# design.net
KiCad netlist of a schematic drawn in Altium Designer
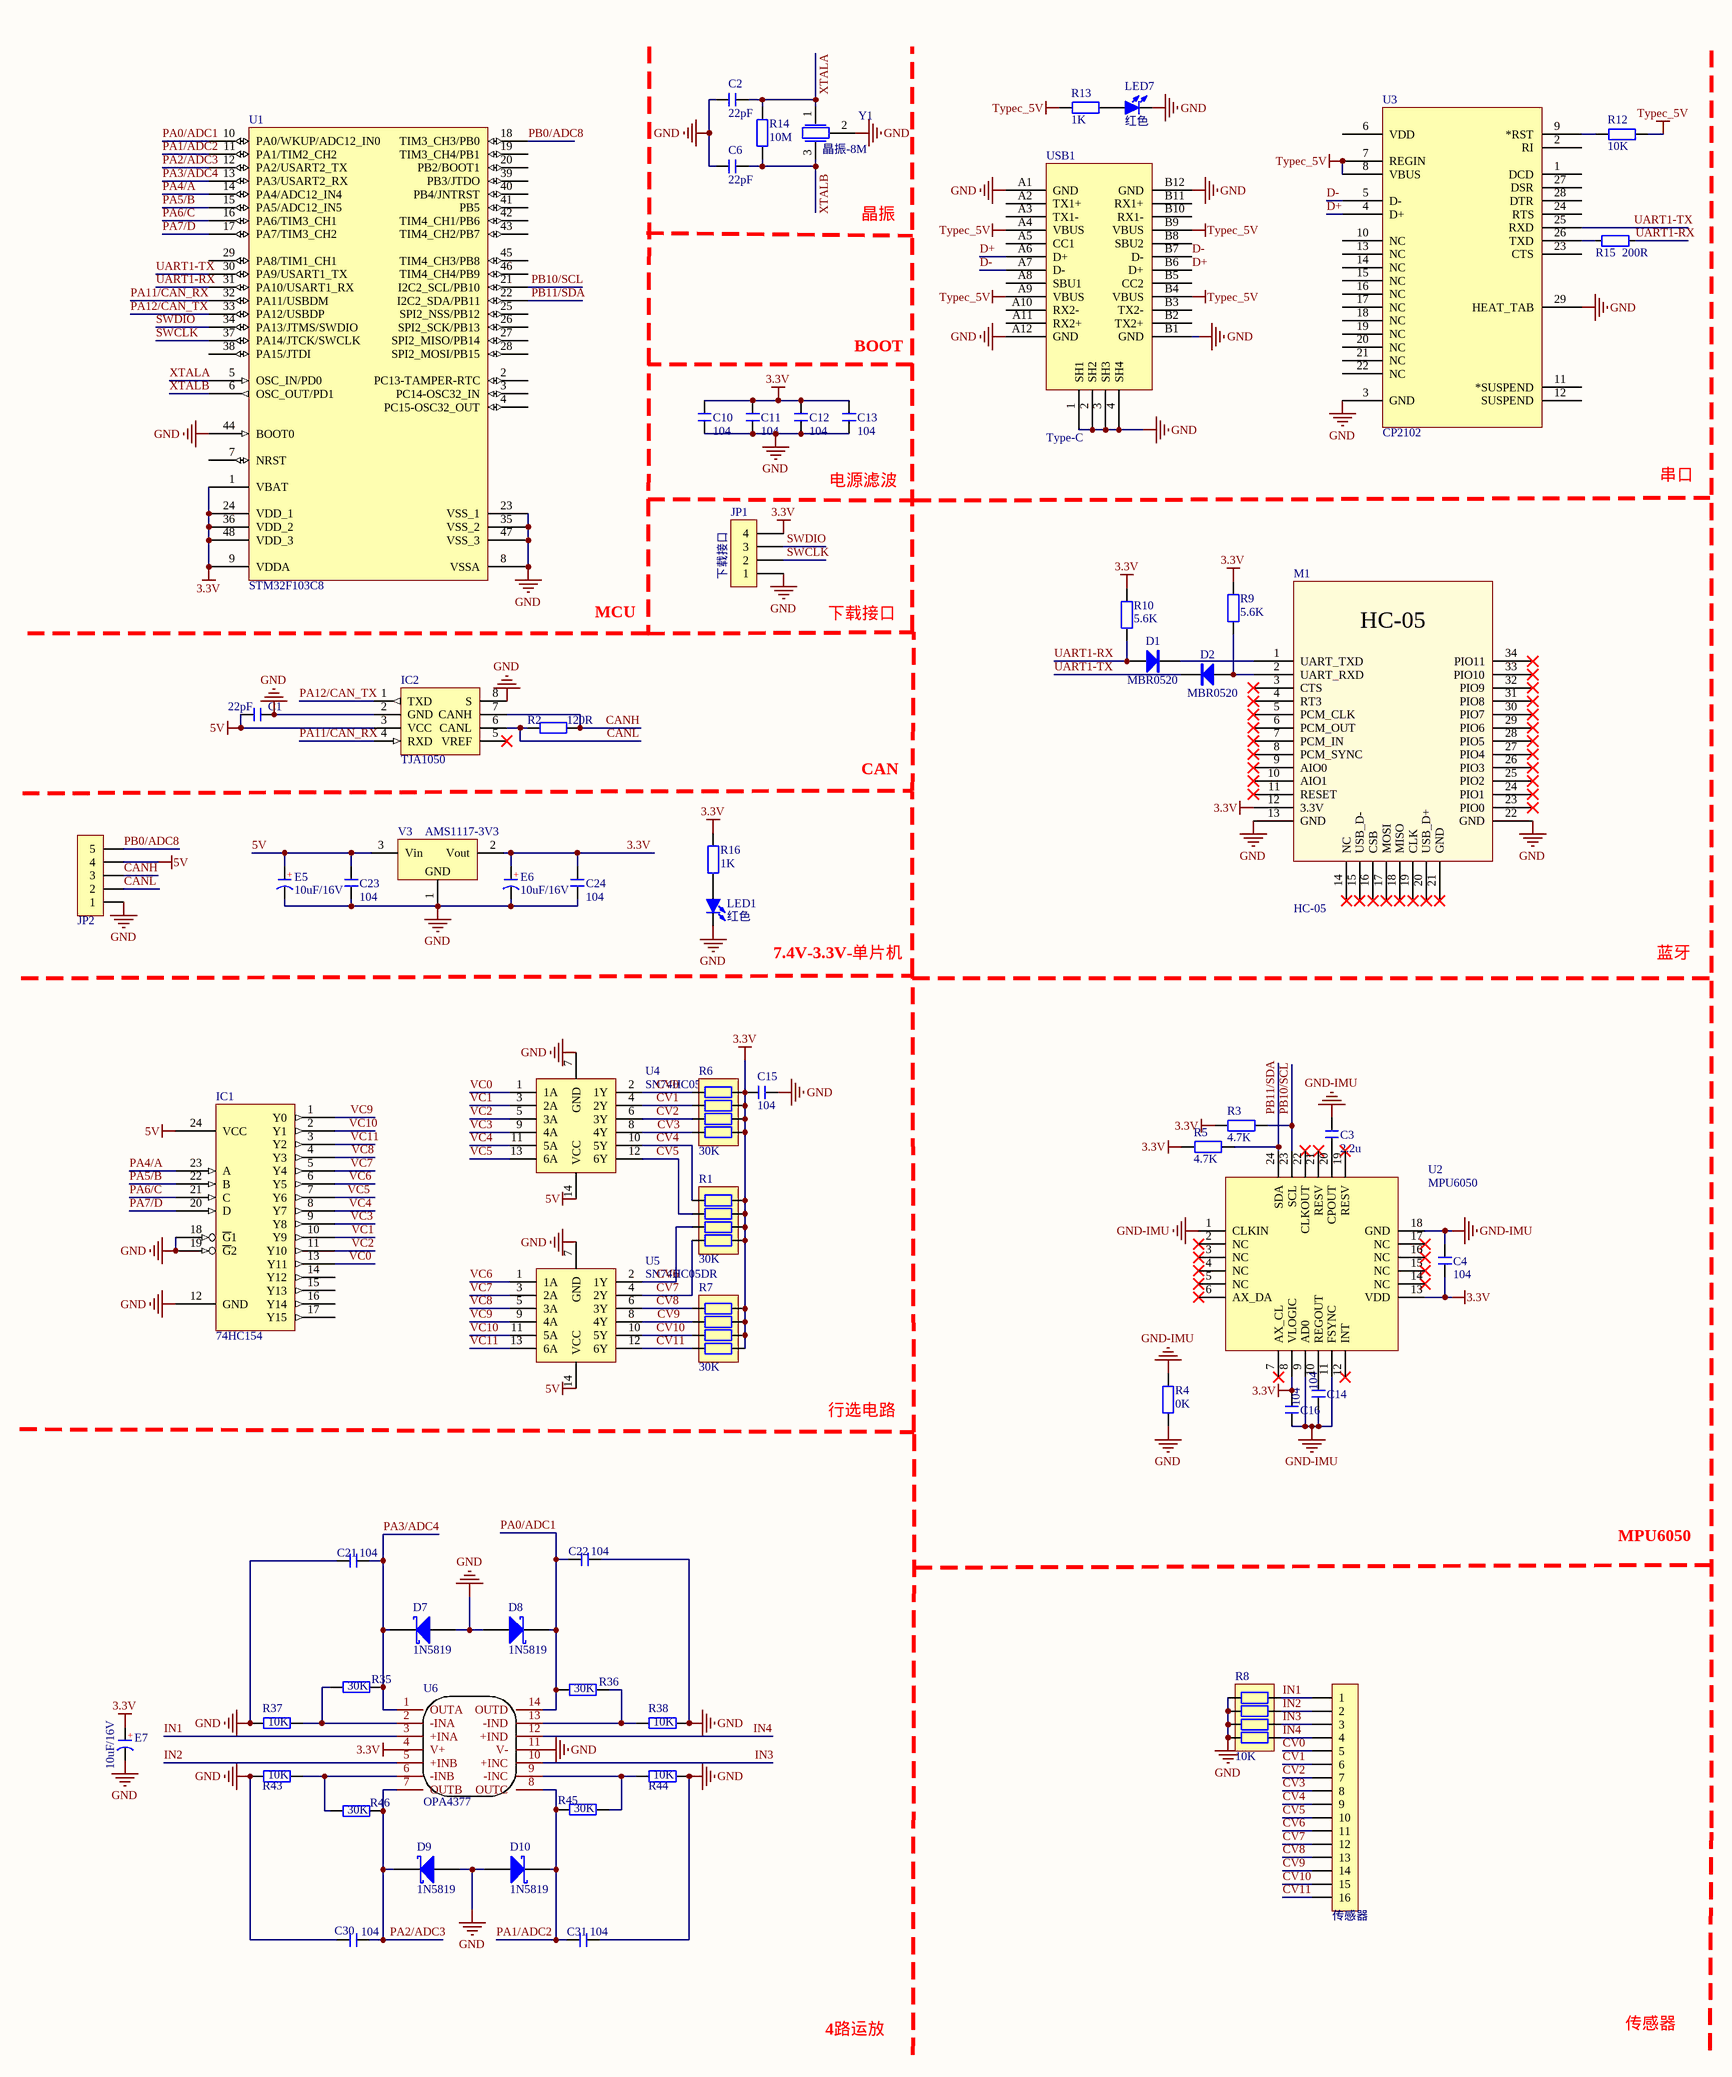
[diagram p0: 足底压力.SchDoc]

(export (version "E")
  (design (tool "Eeschema 10.0.6"))
  (components
    (comp (ref "C1")
      (value "22pF")
      (footprint "C 0402_L")
      (description "贴片电容")
      (libsource (lib "0.1 - 电阻-电容-电感") (part "C"))
    )
    (comp (ref "C2")
      (value "22pF")
      (footprint "C 0402_L")
      (description "贴片电容")
      (libsource (lib "0.1 - 电阻-电容-电感") (part "C"))
    )
    (comp (ref "C3")
      (value "2.2u")
      (footprint "C 0402_L")
      (description "贴片电容")
      (libsource (lib "0.1 - 电阻-电容-电感") (part "C"))
    )
    (comp (ref "C4")
      (value "104")
      (footprint "C 0402_L")
      (description "贴片电容")
      (libsource (lib "0.1 - 电阻-电容-电感") (part "C"))
    )
    (comp (ref "C6")
      (value "22pF")
      (footprint "C 0402_L")
      (description "贴片电容")
      (libsource (lib "0.1 - 电阻-电容-电感") (part "C"))
    )
    (comp (ref "C10")
      (value "104")
      (footprint "C 0402_L")
      (description "贴片电容")
      (libsource (lib "0.1 - 电阻-电容-电感") (part "C"))
    )
    (comp (ref "C11")
      (value "104")
      (footprint "C 0402_L")
      (description "贴片电容")
      (libsource (lib "0.1 - 电阻-电容-电感") (part "C"))
    )
    (comp (ref "C12")
      (value "104")
      (footprint "C 0402_L")
      (description "贴片电容")
      (libsource (lib "0.1 - 电阻-电容-电感") (part "C"))
    )
    (comp (ref "C13")
      (value "104")
      (footprint "C 0402_L")
      (description "贴片电容")
      (libsource (lib "0.1 - 电阻-电容-电感") (part "C"))
    )
    (comp (ref "C14")
      (value "104")
      (footprint "C 0402_L")
      (description "贴片电容")
      (libsource (lib "0.1 - 电阻-电容-电感") (part "C"))
    )
    (comp (ref "C15")
      (value "104")
      (footprint "C 0402_L")
      (description "贴片电容")
      (libsource (lib "0.1 - 电阻-电容-电感") (part "C"))
    )
    (comp (ref "C16")
      (value "104")
      (footprint "C 0402_L")
      (description "贴片电容")
      (libsource (lib "0.1 - 电阻-电容-电感") (part "C"))
    )
    (comp (ref "C21")
      (value "104")
      (footprint "C 0402_L")
      (description "贴片电容")
      (libsource (lib "0.1 - 电阻-电容-电感") (part "C"))
    )
    (comp (ref "C22")
      (value "104")
      (footprint "C 0402_L")
      (description "贴片电容")
      (libsource (lib "0.1 - 电阻-电容-电感") (part "C"))
    )
    (comp (ref "C23")
      (value "104")
      (footprint "C 0402_L")
      (description "贴片电容")
      (libsource (lib "0.1 - 电阻-电容-电感") (part "C"))
    )
    (comp (ref "C24")
      (value "104")
      (footprint "C 0402_L")
      (description "贴片电容")
      (libsource (lib "0.1 - 电阻-电容-电感") (part "C"))
    )
    (comp (ref "C30")
      (value "104")
      (footprint "C 0402_L")
      (description "贴片电容")
      (libsource (lib "0.1 - 电阻-电容-电感") (part "C"))
    )
    (comp (ref "C31")
      (value "104")
      (footprint "C 0402_L")
      (description "贴片电容")
      (libsource (lib "0.1 - 电阻-电容-电感") (part "C"))
    )
    (comp (ref "D1")
      (value "MBR0520")
      (footprint "SOD-123")
      (description "整流二极管")
      (libsource (lib "0.2 -  二极管-整流桥") (part "1N4007"))
    )
    (comp (ref "D2")
      (value "MBR0520")
      (footprint "SOD-123")
      (description "整流二极管")
      (libsource (lib "0.2 -  二极管-整流桥") (part "1N4007"))
    )
    (comp (ref "D7")
      (value "1N5819")
      (footprint "SOD-123")
      (description "肖特基二极管")
      (libsource (lib "0.2 -  二极管-整流桥") (part "1N5819"))
    )
    (comp (ref "D8")
      (value "1N5819")
      (footprint "SOD-123")
      (description "肖特基二极管")
      (libsource (lib "0.2 -  二极管-整流桥") (part "1N5819"))
    )
    (comp (ref "D9")
      (value "1N5819")
      (footprint "SOD-123")
      (description "肖特基二极管")
      (libsource (lib "0.2 -  二极管-整流桥") (part "1N5819"))
    )
    (comp (ref "D10")
      (value "1N5819")
      (footprint "SOD-123")
      (description "肖特基二极管")
      (libsource (lib "0.2 -  二极管-整流桥") (part "1N5819"))
    )
    (comp (ref "E5")
      (value "10uF/16V")
      (footprint "CD A(3216)")
      (description "贴片钽电容")
      (libsource (lib "0.1 - 电阻-电容-电感") (part "CT"))
    )
    (comp (ref "E6")
      (value "10uF/16V")
      (footprint "CD A(3216)")
      (description "贴片钽电容")
      (libsource (lib "0.1 - 电阻-电容-电感") (part "CT"))
    )
    (comp (ref "E7")
      (value "10uF/16V")
      (footprint "CD A(3216)")
      (description "贴片钽电容")
      (libsource (lib "0.1 - 电阻-电容-电感") (part "CT"))
    )
    (comp (ref "IC1")
      (value "74HC154")
      (footprint "SOP24_N")
      (description "4线转16线译码器")
      (libsource (lib "74系列芯片") (part "74HC154"))
    )
    (comp (ref "IC2")
      (value "TJA1050")
      (footprint "SOP8_L")
      (description "CAN总线收发芯片")
      (libsource (lib "1.0 - 常见芯片") (part "TJA1050"))
    )
    (comp (ref "JP1")
      (value "下载接口")
      (footprint "下载接口")
      (description "Jlink下载接口")
      (libsource (lib "金手指") (part "下载接口"))
    )
    (comp (ref "JP2")
      (value "HDR-1X5")
      (footprint "HDR2.54-M-LI-5P")
      (description "5P接插件")
      (libsource (lib "5.3 - 接插件-脚距2.54 (100mil) ") (part "Header 5"))
    )
    (comp (ref "LED1")
      (value "红色")
      (footprint "LED 0603R")
      (description "贴片LED")
      (libsource (lib "0.3 - LED发光二极管") (part "LED-SMD"))
    )
    (comp (ref "LED7")
      (value "红色")
      (footprint "LED 0603R")
      (description "贴片LED")
      (libsource (lib "0.3 - LED发光二极管") (part "LED-SMD"))
    )
    (comp (ref "M1")
      (value "HC-05")
      (footprint "HC-05")
      (description "串口蓝牙模块")
      (libsource (lib "模块") (part "HC-05"))
    )
    (comp (ref "R1")
      (value "30K")
      (footprint "RCA-8P4R-0603")
      (description "贴片排阻")
      (libsource (lib "0.1 - 电阻-电容-电感") (part "R-8P4R"))
    )
    (comp (ref "R2")
      (value "120R")
      (footprint "R 0402_L")
      (description "贴片电阻")
      (libsource (lib "0.1 - 电阻-电容-电感") (part "R"))
    )
    (comp (ref "R3")
      (value "4.7K")
      (footprint "R 0402_L")
      (description "贴片电阻")
      (libsource (lib "0.1 - 电阻-电容-电感") (part "R"))
    )
    (comp (ref "R4")
      (value "0K")
      (footprint "R 0402_L")
      (description "贴片电阻")
      (libsource (lib "0.1 - 电阻-电容-电感") (part "R"))
    )
    (comp (ref "R5")
      (value "4.7K")
      (footprint "R 0402_L")
      (description "贴片电阻")
      (libsource (lib "0.1 - 电阻-电容-电感") (part "R"))
    )
    (comp (ref "R6")
      (value "30K")
      (footprint "RCA-8P4R-0603")
      (description "贴片排阻")
      (libsource (lib "0.1 - 电阻-电容-电感") (part "R-8P4R"))
    )
    (comp (ref "R7")
      (value "30K")
      (footprint "RCA-8P4R-0603")
      (description "贴片排阻")
      (libsource (lib "0.1 - 电阻-电容-电感") (part "R-8P4R"))
    )
    (comp (ref "R8")
      (value "10K")
      (footprint "RCA-8P4R-0603")
      (description "贴片排阻")
      (libsource (lib "") (part "R-8P4R_1"))
    )
    (comp (ref "R9")
      (value "5.6K")
      (footprint "R 0402_L")
      (description "贴片电阻")
      (libsource (lib "0.1 - 电阻-电容-电感") (part "R"))
    )
    (comp (ref "R10")
      (value "5.6K")
      (footprint "R 0402_L")
      (description "贴片电阻")
      (libsource (lib "0.1 - 电阻-电容-电感") (part "R"))
    )
    (comp (ref "R12")
      (value "10K")
      (footprint "R 0402_L")
      (description "贴片电阻")
      (libsource (lib "0.1 - 电阻-电容-电感") (part "R"))
    )
    (comp (ref "R13")
      (value "1K")
      (footprint "R 0402_L")
      (description "贴片电阻")
      (libsource (lib "0.1 - 电阻-电容-电感") (part "R"))
    )
    (comp (ref "R14")
      (value "10M")
      (footprint "R 0402_L")
      (description "贴片电阻")
      (libsource (lib "0.1 - 电阻-电容-电感") (part "R"))
    )
    (comp (ref "R15")
      (value "200R")
      (footprint "RES_0402")
      (description "Resistor")
      (libsource (lib "MyPcbLib") (part "电阻-0402"))
    )
    (comp (ref "R16")
      (value "1K")
      (footprint "R 0402_L")
      (description "贴片电阻")
      (libsource (lib "0.1 - 电阻-电容-电感") (part "R"))
    )
    (comp (ref "R35")
      (value "30K")
      (footprint "R 0402_L")
      (description "贴片电阻")
      (libsource (lib "0.1 - 电阻-电容-电感") (part "R"))
    )
    (comp (ref "R36")
      (value "30K")
      (footprint "R 0402_L")
      (description "贴片电阻")
      (libsource (lib "0.1 - 电阻-电容-电感") (part "R"))
    )
    (comp (ref "R37")
      (value "10K")
      (footprint "R 0402_L")
      (description "贴片电阻")
      (libsource (lib "0.1 - 电阻-电容-电感") (part "R"))
    )
    (comp (ref "R38")
      (value "10K")
      (footprint "R 0402_L")
      (description "贴片电阻")
      (libsource (lib "0.1 - 电阻-电容-电感") (part "R"))
    )
    (comp (ref "R43")
      (value "10K")
      (footprint "R 0402_L")
      (description "贴片电阻")
      (libsource (lib "0.1 - 电阻-电容-电感") (part "R"))
    )
    (comp (ref "R44")
      (value "10K")
      (footprint "R 0402_L")
      (description "贴片电阻")
      (libsource (lib "0.1 - 电阻-电容-电感") (part "R"))
    )
    (comp (ref "R45")
      (value "30K")
      (footprint "R 0402_L")
      (description "贴片电阻")
      (libsource (lib "0.1 - 电阻-电容-电感") (part "R"))
    )
    (comp (ref "R46")
      (value "30K")
      (footprint "R 0402_L")
      (description "贴片电阻")
      (libsource (lib "0.1 - 电阻-电容-电感") (part "R"))
    )
    (comp (ref "U1")
      (value "STM32F103C8")
      (footprint "LQFP48 7X7_L")
      (description "Flaah:64/RAM:20/IO:36")
      (libsource (lib "STM32系列单片机") (part "STM32F103C8"))
    )
    (comp (ref "U2")
      (value "MPU6050")
      (footprint "QFN24 4x4_L")
      (description "数字运动传感器")
      (libsource (lib "传感元件") (part "MPU6050"))
    )
    (comp (ref "U3")
      (value "CP2102")
      (footprint "QFN-28")
      (description "USB转TTL")
      (libsource (lib "mLib") (part "CP2102"))
    )
    (comp (ref "U4")
      (value "SN74HC05DR")
      (footprint "SOP14")
      (libsource (lib "1.4 - 74系列TTL芯片") (part "SN74HC05DR"))
    )
    (comp (ref "U5")
      (value "SN74HC05DR")
      (footprint "SOP14")
      (libsource (lib "1.4 - 74系列TTL芯片") (part "SN74HC05DR"))
    )
    (comp (ref "U6")
      (value "OPA4377")
      (footprint "TSSOP14_L")
      (description "4路运放")
      (libsource (lib "运放-功放") (part "OPA4377"))
    )
    (comp (ref "USB1")
      (value "Type-C")
      (footprint "USB-C-SMD_16P")
      (libsource (lib "0.8 - 以太网-音频-USB插座") (part "USB-Type-C-TOP"))
    )
    (comp (ref "V3")
      (value "AMS1117-3V3")
      (footprint "SOT223_L")
      (description "三端稳压芯片")
      (libsource (lib "1.1 - 电源类芯片") (part "AMS1117"))
    )
    (comp (ref "Y1")
      (value "晶振-8M")
      (footprint "XTAL3*7")
      (libsource (lib "2.0 - 保险丝-晶振-光耦") (part "XTAL-3P"))
    )
    (comp (ref "传感器")
      (value "HDR-1X16")
      (footprint "XH2.54-WI-16P")
      (description "16P接插件")
      (libsource (lib "5.3 - 接插件-脚距2.54 (100mil) ") (part "Header 16"))
    )
  )
  (nets
    (net (code "1") (name "/CANH") (class "Default")
      (node (ref "IC2") (pin "7") (pinfunction "CANH_7") (pintype "passive"))
      (node (ref "JP2") (pin "3") (pinfunction "3_3") (pintype "passive"))
      (node (ref "R2") (pin "1") (pinfunction "1_1") (pintype "passive"))
    )
    (net (code "2") (name "/CANL") (class "Default")
      (node (ref "IC2") (pin "6") (pinfunction "CANL_6") (pintype "passive"))
      (node (ref "JP2") (pin "2") (pinfunction "2_2") (pintype "passive"))
      (node (ref "R2") (pin "2") (pinfunction "2_2") (pintype "passive"))
    )
    (net (code "3") (name "/CV0") (class "Default")
      (node (ref "R6") (pin "1") (pinfunction "1_1") (pintype "passive"))
      (node (ref "U4") (pin "2") (pinfunction "1Y_2") (pintype "passive"))
      (node (ref "传感器") (pin "5") (pinfunction "5_5") (pintype "passive"))
    )
    (net (code "4") (name "/CV1") (class "Default")
      (node (ref "R6") (pin "2") (pinfunction "2_2") (pintype "passive"))
      (node (ref "U4") (pin "4") (pinfunction "2Y_4") (pintype "passive"))
      (node (ref "传感器") (pin "6") (pinfunction "6_6") (pintype "passive"))
    )
    (net (code "5") (name "/CV2") (class "Default")
      (node (ref "R6") (pin "3") (pinfunction "3_3") (pintype "passive"))
      (node (ref "U4") (pin "6") (pinfunction "3Y_6") (pintype "passive"))
      (node (ref "传感器") (pin "7") (pinfunction "7_7") (pintype "passive"))
    )
    (net (code "6") (name "/CV3") (class "Default")
      (node (ref "R6") (pin "4") (pinfunction "4_4") (pintype "passive"))
      (node (ref "U4") (pin "8") (pinfunction "4Y_8") (pintype "passive"))
      (node (ref "传感器") (pin "8") (pinfunction "8_8") (pintype "passive"))
    )
    (net (code "7") (name "/CV4") (class "Default")
      (node (ref "R1") (pin "1") (pinfunction "1_1") (pintype "passive"))
      (node (ref "U4") (pin "10") (pinfunction "5Y_10") (pintype "passive"))
      (node (ref "传感器") (pin "9") (pinfunction "9_9") (pintype "passive"))
    )
    (net (code "8") (name "/CV5") (class "Default")
      (node (ref "R1") (pin "2") (pinfunction "2_2") (pintype "passive"))
      (node (ref "U4") (pin "12") (pinfunction "6Y_12") (pintype "passive"))
      (node (ref "传感器") (pin "10") (pinfunction "10_10") (pintype "passive"))
    )
    (net (code "9") (name "/CV6") (class "Default")
      (node (ref "R1") (pin "3") (pinfunction "3_3") (pintype "passive"))
      (node (ref "U5") (pin "2") (pinfunction "1Y_2") (pintype "passive"))
      (node (ref "传感器") (pin "11") (pinfunction "11_11") (pintype "passive"))
    )
    (net (code "10") (name "/CV7") (class "Default")
      (node (ref "R1") (pin "4") (pinfunction "4_4") (pintype "passive"))
      (node (ref "U5") (pin "4") (pinfunction "2Y_4") (pintype "passive"))
      (node (ref "传感器") (pin "12") (pinfunction "12_12") (pintype "passive"))
    )
    (net (code "11") (name "/CV8") (class "Default")
      (node (ref "R7") (pin "1") (pinfunction "1_1") (pintype "passive"))
      (node (ref "U5") (pin "6") (pinfunction "3Y_6") (pintype "passive"))
      (node (ref "传感器") (pin "13") (pinfunction "13_13") (pintype "passive"))
    )
    (net (code "12") (name "/CV9") (class "Default")
      (node (ref "R7") (pin "2") (pinfunction "2_2") (pintype "passive"))
      (node (ref "U5") (pin "8") (pinfunction "4Y_8") (pintype "passive"))
      (node (ref "传感器") (pin "14") (pinfunction "14_14") (pintype "passive"))
    )
    (net (code "13") (name "/CV10") (class "Default")
      (node (ref "R7") (pin "3") (pinfunction "3_3") (pintype "passive"))
      (node (ref "U5") (pin "10") (pinfunction "5Y_10") (pintype "passive"))
      (node (ref "传感器") (pin "15") (pinfunction "15_15") (pintype "passive"))
    )
    (net (code "14") (name "/CV11") (class "Default")
      (node (ref "R7") (pin "4") (pinfunction "4_4") (pintype "passive"))
      (node (ref "U5") (pin "12") (pinfunction "6Y_12") (pintype "passive"))
      (node (ref "传感器") (pin "16") (pinfunction "16_16") (pintype "passive"))
    )
    (net (code "15") (name "/D+") (class "Default")
      (node (ref "U3") (pin "4") (pinfunction "D+_4") (pintype "passive"))
      (node (ref "USB1") (pin "A6") (pinfunction "D+_A6") (pintype "passive"))
      (node (ref "USB1") (pin "B6") (pinfunction "D+_B6") (pintype "passive"))
    )
    (net (code "16") (name "/D-") (class "Default")
      (node (ref "U3") (pin "5") (pinfunction "D-_5") (pintype "passive"))
      (node (ref "USB1") (pin "A7") (pinfunction "D-_A7") (pintype "passive"))
      (node (ref "USB1") (pin "B7") (pinfunction "D-_B7") (pintype "passive"))
    )
    (net (code "17") (name "/IN1") (class "Default")
      (node (ref "R8") (pin "5") (pinfunction "5_5") (pintype "passive"))
      (node (ref "U6") (pin "3") (pinfunction "+INA_3") (pintype "passive"))
      (node (ref "传感器") (pin "1") (pinfunction "1_1") (pintype "passive"))
    )
    (net (code "18") (name "/IN2") (class "Default")
      (node (ref "R8") (pin "6") (pinfunction "6_6") (pintype "passive"))
      (node (ref "U6") (pin "5") (pinfunction "+INB_5") (pintype "passive"))
      (node (ref "传感器") (pin "2") (pinfunction "2_2") (pintype "passive"))
    )
    (net (code "19") (name "/IN3") (class "Default")
      (node (ref "R8") (pin "7") (pinfunction "7_7") (pintype "passive"))
      (node (ref "U6") (pin "10") (pinfunction "+INC_10") (pintype "passive"))
      (node (ref "传感器") (pin "3") (pinfunction "3_3") (pintype "passive"))
    )
    (net (code "20") (name "/IN4") (class "Default")
      (node (ref "R8") (pin "8") (pinfunction "8_8") (pintype "passive"))
      (node (ref "U6") (pin "12") (pinfunction "+IND_12") (pintype "passive"))
      (node (ref "传感器") (pin "4") (pinfunction "4_4") (pintype "passive"))
    )
    (net (code "21") (name "/PA0{slash}ADC1") (class "Default")
      (node (ref "C22") (pin "1") (pinfunction "1_1") (pintype "passive"))
      (node (ref "D8") (pin "2") (pinfunction "K_2") (pintype "passive"))
      (node (ref "R36") (pin "1") (pinfunction "1_1") (pintype "passive"))
      (node (ref "U1") (pin "10") (pinfunction "PA0/WKUP/ADC12_IN0_10") (pintype "bidirectional"))
      (node (ref "U6") (pin "14") (pinfunction "OUTD_14") (pintype "passive"))
    )
    (net (code "22") (name "/PA1{slash}ADC2") (class "Default")
      (node (ref "C31") (pin "1") (pinfunction "1_1") (pintype "passive"))
      (node (ref "D10") (pin "2") (pinfunction "K_2") (pintype "passive"))
      (node (ref "R45") (pin "1") (pinfunction "1_1") (pintype "passive"))
      (node (ref "U1") (pin "11") (pinfunction "PA1/TIM2_CH2_11") (pintype "bidirectional"))
      (node (ref "U6") (pin "8") (pinfunction "OUTC_8") (pintype "passive"))
    )
    (net (code "23") (name "/PA2{slash}ADC3") (class "Default")
      (node (ref "C30") (pin "1") (pinfunction "1_1") (pintype "passive"))
      (node (ref "D9") (pin "2") (pinfunction "K_2") (pintype "passive"))
      (node (ref "R46") (pin "2") (pinfunction "2_2") (pintype "passive"))
      (node (ref "U1") (pin "12") (pinfunction "PA2/USART2_TX_12") (pintype "bidirectional"))
      (node (ref "U6") (pin "7") (pinfunction "OUTB_7") (pintype "passive"))
    )
    (net (code "24") (name "/PA3{slash}ADC4") (class "Default")
      (node (ref "C21") (pin "2") (pinfunction "2_2") (pintype "passive"))
      (node (ref "D7") (pin "2") (pinfunction "K_2") (pintype "passive"))
      (node (ref "R35") (pin "2") (pinfunction "2_2") (pintype "passive"))
      (node (ref "U1") (pin "13") (pinfunction "PA3/USART2_RX_13") (pintype "bidirectional"))
      (node (ref "U6") (pin "1") (pinfunction "OUTA_1") (pintype "passive"))
    )
    (net (code "25") (name "/PA4{slash}A") (class "Default")
      (node (ref "IC1") (pin "23") (pinfunction "A_23") (pintype "input"))
      (node (ref "U1") (pin "14") (pinfunction "PA4/ADC12_IN4_14") (pintype "bidirectional"))
    )
    (net (code "26") (name "/PA5{slash}B") (class "Default")
      (node (ref "IC1") (pin "22") (pinfunction "B_22") (pintype "input"))
      (node (ref "U1") (pin "15") (pinfunction "PA5/ADC12_IN5_15") (pintype "bidirectional"))
    )
    (net (code "27") (name "/PA6{slash}C") (class "Default")
      (node (ref "IC1") (pin "21") (pinfunction "C_21") (pintype "input"))
      (node (ref "U1") (pin "16") (pinfunction "PA6/TIM3_CH1_16") (pintype "bidirectional"))
    )
    (net (code "28") (name "/PA7{slash}D") (class "Default")
      (node (ref "IC1") (pin "20") (pinfunction "D_20") (pintype "input"))
      (node (ref "U1") (pin "17") (pinfunction "PA7/TIM3_CH2_17") (pintype "bidirectional"))
    )
    (net (code "29") (name "/PA11{slash}CAN_RX") (class "Default")
      (node (ref "IC2") (pin "4") (pinfunction "RXD_4") (pintype "input"))
      (node (ref "U1") (pin "32") (pinfunction "PA11/USBDM_32") (pintype "bidirectional"))
    )
    (net (code "30") (name "/PA12{slash}CAN_TX") (class "Default")
      (node (ref "IC2") (pin "1") (pinfunction "TXD_1") (pintype "output"))
      (node (ref "U1") (pin "33") (pinfunction "PA12/USBDP_33") (pintype "bidirectional"))
    )
    (net (code "31") (name "/PB0{slash}ADC8") (class "Default")
      (node (ref "JP2") (pin "5") (pinfunction "5_5") (pintype "passive"))
      (node (ref "U1") (pin "18") (pinfunction "TIM3_CH3/PB0_18") (pintype "bidirectional"))
    )
    (net (code "32") (name "/PB10{slash}SCL") (class "Default")
      (node (ref "R3") (pin "2") (pinfunction "2_2") (pintype "passive"))
      (node (ref "U1") (pin "21") (pinfunction "I2C2_SCL/PB10_21") (pintype "bidirectional"))
      (node (ref "U2") (pin "23") (pinfunction "SCL_23") (pintype "passive"))
    )
    (net (code "33") (name "/PB11{slash}SDA") (class "Default")
      (node (ref "R5") (pin "2") (pinfunction "2_2") (pintype "passive"))
      (node (ref "U1") (pin "22") (pinfunction "I2C2_SDA/PB11_22") (pintype "bidirectional"))
      (node (ref "U2") (pin "24") (pinfunction "SDA_24") (pintype "passive"))
    )
    (net (code "34") (name "/SWCLK") (class "Default")
      (node (ref "JP1") (pin "2") (pinfunction "2_2") (pintype "passive"))
      (node (ref "U1") (pin "37") (pinfunction "PA14/JTCK/SWCLK_37") (pintype "bidirectional"))
    )
    (net (code "35") (name "/SWDIO") (class "Default")
      (node (ref "JP1") (pin "3") (pinfunction "3_3") (pintype "passive"))
      (node (ref "U1") (pin "34") (pinfunction "PA13/JTMS/SWDIO_34") (pintype "bidirectional"))
    )
    (net (code "36") (name "/UART1-RX") (class "Default")
      (node (ref "D1") (pin "1") (pinfunction "A_1") (pintype "passive"))
      (node (ref "R10") (pin "1") (pinfunction "1_1") (pintype "passive"))
      (node (ref "R15") (pin "1") (pinfunction "1_1") (pintype "passive"))
      (node (ref "U1") (pin "31") (pinfunction "PA10/USART1_RX_31") (pintype "bidirectional"))
    )
    (net (code "37") (name "/UART1-TX") (class "Default")
      (node (ref "D2") (pin "2") (pinfunction "K_2") (pintype "passive"))
      (node (ref "U1") (pin "30") (pinfunction "PA9/USART1_TX_30") (pintype "bidirectional"))
      (node (ref "U3") (pin "25") (pinfunction "RXD_25") (pintype "passive"))
    )
    (net (code "38") (name "/VC0") (class "Default")
      (node (ref "IC1") (pin "13") (pinfunction "Y11_13") (pintype "output"))
      (node (ref "U4") (pin "1") (pinfunction "1A_1") (pintype "passive"))
    )
    (net (code "39") (name "/VC1") (class "Default")
      (node (ref "IC1") (pin "10") (pinfunction "Y9_10") (pintype "output"))
      (node (ref "U4") (pin "3") (pinfunction "2A_3") (pintype "passive"))
    )
    (net (code "40") (name "/VC2") (class "Default")
      (node (ref "IC1") (pin "11") (pinfunction "Y10_11") (pintype "output"))
      (node (ref "U4") (pin "5") (pinfunction "3A_5") (pintype "passive"))
    )
    (net (code "41") (name "/VC3") (class "Default")
      (node (ref "IC1") (pin "9") (pinfunction "Y8_9") (pintype "output"))
      (node (ref "U4") (pin "9") (pinfunction "4A_9") (pintype "passive"))
    )
    (net (code "42") (name "/VC4") (class "Default")
      (node (ref "IC1") (pin "8") (pinfunction "Y7_8") (pintype "output"))
      (node (ref "U4") (pin "11") (pinfunction "5A_11") (pintype "passive"))
    )
    (net (code "43") (name "/VC5") (class "Default")
      (node (ref "IC1") (pin "7") (pinfunction "Y6_7") (pintype "output"))
      (node (ref "U4") (pin "13") (pinfunction "6A_13") (pintype "passive"))
    )
    (net (code "44") (name "/VC6") (class "Default")
      (node (ref "IC1") (pin "6") (pinfunction "Y5_6") (pintype "output"))
      (node (ref "U5") (pin "1") (pinfunction "1A_1") (pintype "passive"))
    )
    (net (code "45") (name "/VC7") (class "Default")
      (node (ref "IC1") (pin "5") (pinfunction "Y4_5") (pintype "output"))
      (node (ref "U5") (pin "3") (pinfunction "2A_3") (pintype "passive"))
    )
    (net (code "46") (name "/VC8") (class "Default")
      (node (ref "IC1") (pin "4") (pinfunction "Y3_4") (pintype "output"))
      (node (ref "U5") (pin "5") (pinfunction "3A_5") (pintype "passive"))
    )
    (net (code "47") (name "/VC9") (class "Default")
      (node (ref "IC1") (pin "1") (pinfunction "Y0_1") (pintype "output"))
      (node (ref "U5") (pin "9") (pinfunction "4A_9") (pintype "passive"))
    )
    (net (code "48") (name "/VC10") (class "Default")
      (node (ref "IC1") (pin "2") (pinfunction "Y1_2") (pintype "output"))
      (node (ref "U5") (pin "11") (pinfunction "5A_11") (pintype "passive"))
    )
    (net (code "49") (name "/VC11") (class "Default")
      (node (ref "IC1") (pin "3") (pinfunction "Y2_3") (pintype "output"))
      (node (ref "U5") (pin "13") (pinfunction "6A_13") (pintype "passive"))
    )
    (net (code "50") (name "/XTALA") (class "Default")
      (node (ref "C2") (pin "2") (pinfunction "2_2") (pintype "passive"))
      (node (ref "R14") (pin "1") (pinfunction "1_1") (pintype "passive"))
      (node (ref "U1") (pin "5") (pinfunction "OSC_IN/PD0_5") (pintype "input"))
      (node (ref "Y1") (pin "1") (pinfunction "1_1") (pintype "passive"))
    )
    (net (code "51") (name "/XTALB") (class "Default")
      (node (ref "C6") (pin "2") (pinfunction "2_2") (pintype "passive"))
      (node (ref "R14") (pin "2") (pinfunction "2_2") (pintype "passive"))
      (node (ref "U1") (pin "6") (pinfunction "OSC_OUT/PD1_6") (pintype "output"))
      (node (ref "Y1") (pin "3") (pinfunction "3_3") (pintype "passive"))
    )
    (net (code "52") (name "3.3V") (class "Default")
      (node (ref "C10") (pin "2") (pinfunction "2_2") (pintype "passive"))
      (node (ref "C11") (pin "2") (pinfunction "2_2") (pintype "passive"))
      (node (ref "C12") (pin "2") (pinfunction "2_2") (pintype "passive"))
      (node (ref "C13") (pin "2") (pinfunction "2_2") (pintype "passive"))
      (node (ref "C15") (pin "1") (pinfunction "1_1") (pintype "passive"))
      (node (ref "C16") (pin "2") (pinfunction "2_2") (pintype "passive"))
      (node (ref "C24") (pin "2") (pinfunction "2_2") (pintype "passive"))
      (node (ref "C4") (pin "1") (pinfunction "1_1") (pintype "passive"))
      (node (ref "E6") (pin "1") (pinfunction "A_1") (pintype "passive"))
      (node (ref "E7") (pin "1") (pinfunction "A_1") (pintype "passive"))
      (node (ref "JP1") (pin "4") (pinfunction "4_4") (pintype "passive"))
      (node (ref "M1") (pin "12") (pinfunction "3.3V_12") (pintype "passive"))
      (node (ref "R1") (pin "5") (pinfunction "5_5") (pintype "passive"))
      (node (ref "R1") (pin "6") (pinfunction "6_6") (pintype "passive"))
      (node (ref "R1") (pin "7") (pinfunction "7_7") (pintype "passive"))
      (node (ref "R1") (pin "8") (pinfunction "8_8") (pintype "passive"))
      (node (ref "R10") (pin "2") (pinfunction "2_2") (pintype "passive"))
      (node (ref "R16") (pin "2") (pinfunction "2_2") (pintype "passive"))
      (node (ref "R3") (pin "1") (pinfunction "1_1") (pintype "passive"))
      (node (ref "R5") (pin "1") (pinfunction "1_1") (pintype "passive"))
      (node (ref "R6") (pin "5") (pinfunction "5_5") (pintype "passive"))
      (node (ref "R6") (pin "6") (pinfunction "6_6") (pintype "passive"))
      (node (ref "R6") (pin "7") (pinfunction "7_7") (pintype "passive"))
      (node (ref "R6") (pin "8") (pinfunction "8_8") (pintype "passive"))
      (node (ref "R7") (pin "5") (pinfunction "5_5") (pintype "passive"))
      (node (ref "R7") (pin "6") (pinfunction "6_6") (pintype "passive"))
      (node (ref "R7") (pin "7") (pinfunction "7_7") (pintype "passive"))
      (node (ref "R7") (pin "8") (pinfunction "8_8") (pintype "passive"))
      (node (ref "R9") (pin "2") (pinfunction "2_2") (pintype "passive"))
      (node (ref "U1") (pin "1") (pinfunction "VBAT_1") (pintype "power_in"))
      (node (ref "U1") (pin "24") (pinfunction "VDD_1_24") (pintype "power_in"))
      (node (ref "U1") (pin "36") (pinfunction "VDD_2_36") (pintype "power_in"))
      (node (ref "U1") (pin "48") (pinfunction "VDD_3_48") (pintype "power_in"))
      (node (ref "U1") (pin "9") (pinfunction "VDDA_9") (pintype "power_in"))
      (node (ref "U2") (pin "13") (pinfunction "VDD_13") (pintype "passive"))
      (node (ref "U2") (pin "8") (pinfunction "VLOGIC_8") (pintype "passive"))
      (node (ref "U6") (pin "4") (pinfunction "V+_4") (pintype "passive"))
      (node (ref "V3") (pin "2") (pinfunction "Vout_2") (pintype "passive"))
    )
    (net (code "53") (name "5V") (class "Default")
      (node (ref "C1") (pin "2") (pinfunction "2_2") (pintype "passive"))
      (node (ref "C23") (pin "2") (pinfunction "2_2") (pintype "passive"))
      (node (ref "E5") (pin "1") (pinfunction "A_1") (pintype "passive"))
      (node (ref "IC1") (pin "24") (pinfunction "VCC_24") (pintype "power_in"))
      (node (ref "IC2") (pin "3") (pinfunction "VCC_3") (pintype "passive"))
      (node (ref "JP2") (pin "4") (pinfunction "4_4") (pintype "passive"))
      (node (ref "U4") (pin "14") (pinfunction "VCC_14") (pintype "passive"))
      (node (ref "U5") (pin "14") (pinfunction "VCC_14") (pintype "passive"))
      (node (ref "V3") (pin "3") (pinfunction "Vin_3") (pintype "passive"))
    )
    (net (code "54") (name "GND") (class "Default")
      (node (ref "C1") (pin "1") (pinfunction "1_1") (pintype "passive"))
      (node (ref "C10") (pin "1") (pinfunction "1_1") (pintype "passive"))
      (node (ref "C11") (pin "1") (pinfunction "1_1") (pintype "passive"))
      (node (ref "C12") (pin "1") (pinfunction "1_1") (pintype "passive"))
      (node (ref "C13") (pin "1") (pinfunction "1_1") (pintype "passive"))
      (node (ref "C15") (pin "2") (pinfunction "2_2") (pintype "passive"))
      (node (ref "C2") (pin "1") (pinfunction "1_1") (pintype "passive"))
      (node (ref "C21") (pin "1") (pinfunction "1_1") (pintype "passive"))
      (node (ref "C22") (pin "2") (pinfunction "2_2") (pintype "passive"))
      (node (ref "C23") (pin "1") (pinfunction "1_1") (pintype "passive"))
      (node (ref "C24") (pin "1") (pinfunction "1_1") (pintype "passive"))
      (node (ref "C30") (pin "2") (pinfunction "2_2") (pintype "passive"))
      (node (ref "C31") (pin "2") (pinfunction "2_2") (pintype "passive"))
      (node (ref "C6") (pin "1") (pinfunction "1_1") (pintype "passive"))
      (node (ref "D10") (pin "1") (pinfunction "A_1") (pintype "passive"))
      (node (ref "D7") (pin "1") (pinfunction "A_1") (pintype "passive"))
      (node (ref "D8") (pin "1") (pinfunction "A_1") (pintype "passive"))
      (node (ref "D9") (pin "1") (pinfunction "A_1") (pintype "passive"))
      (node (ref "E5") (pin "2") (pinfunction "K_2") (pintype "passive"))
      (node (ref "E6") (pin "2") (pinfunction "K_2") (pintype "passive"))
      (node (ref "E7") (pin "2") (pinfunction "K_2") (pintype "passive"))
      (node (ref "IC1") (pin "12") (pinfunction "GND_12") (pintype "power_in"))
      (node (ref "IC1") (pin "18") (pinfunction "~{G}1_18") (pintype "input"))
      (node (ref "IC1") (pin "19") (pinfunction "~{G}2_19") (pintype "input"))
      (node (ref "IC2") (pin "2") (pinfunction "GND_2") (pintype "passive"))
      (node (ref "IC2") (pin "8") (pinfunction "S_8") (pintype "passive"))
      (node (ref "JP1") (pin "1") (pinfunction "1_1") (pintype "passive"))
      (node (ref "JP2") (pin "1") (pinfunction "1_1") (pintype "passive"))
      (node (ref "LED1") (pin "2") (pinfunction "K_2") (pintype "passive"))
      (node (ref "LED7") (pin "2") (pinfunction "K_2") (pintype "passive"))
      (node (ref "M1") (pin "13") (pinfunction "GND_13") (pintype "passive"))
      (node (ref "M1") (pin "22") (pinfunction "GND_22") (pintype "passive"))
      (node (ref "R37") (pin "2") (pinfunction "2_2") (pintype "passive"))
      (node (ref "R38") (pin "1") (pinfunction "1_1") (pintype "passive"))
      (node (ref "R4") (pin "1") (pinfunction "1_1") (pintype "passive"))
      (node (ref "R43") (pin "1") (pinfunction "1_1") (pintype "passive"))
      (node (ref "R44") (pin "2") (pinfunction "2_2") (pintype "passive"))
      (node (ref "R8") (pin "1") (pinfunction "1_1") (pintype "passive"))
      (node (ref "R8") (pin "2") (pinfunction "2_2") (pintype "passive"))
      (node (ref "R8") (pin "3") (pinfunction "3_3") (pintype "passive"))
      (node (ref "R8") (pin "4") (pinfunction "4_4") (pintype "passive"))
      (node (ref "U1") (pin "23") (pinfunction "VSS_1_23") (pintype "power_in"))
      (node (ref "U1") (pin "35") (pinfunction "VSS_2_35") (pintype "power_in"))
      (node (ref "U1") (pin "44") (pinfunction "BOOT0_44") (pintype "input"))
      (node (ref "U1") (pin "47") (pinfunction "VSS_3_47") (pintype "power_in"))
      (node (ref "U1") (pin "8") (pinfunction "VSSA_8") (pintype "power_in"))
      (node (ref "U3") (pin "29") (pinfunction "HEAT_TAB_29") (pintype "passive"))
      (node (ref "U3") (pin "3") (pinfunction "GND_3") (pintype "passive"))
      (node (ref "U4") (pin "7") (pinfunction "GND_7") (pintype "passive"))
      (node (ref "U5") (pin "7") (pinfunction "GND_7") (pintype "passive"))
      (node (ref "U6") (pin "11") (pinfunction "V-_11") (pintype "passive"))
      (node (ref "USB1") (pin "1") (pinfunction "SH1_1") (pintype "passive"))
      (node (ref "USB1") (pin "2") (pinfunction "SH2_2") (pintype "passive"))
      (node (ref "USB1") (pin "3") (pinfunction "SH3_3") (pintype "passive"))
      (node (ref "USB1") (pin "4") (pinfunction "SH4_4") (pintype "passive"))
      (node (ref "USB1") (pin "A1") (pinfunction "GND_A1") (pintype "passive"))
      (node (ref "USB1") (pin "A12") (pinfunction "GND_A12") (pintype "passive"))
      (node (ref "USB1") (pin "B1") (pinfunction "GND_B1") (pintype "passive"))
      (node (ref "USB1") (pin "B12") (pinfunction "GND_B12") (pintype "passive"))
      (node (ref "V3") (pin "1") (pinfunction "GND_1") (pintype "passive"))
      (node (ref "Y1") (pin "2") (pinfunction "2_2") (pintype "passive"))
    )
    (net (code "55") (name "GND-IMU") (class "Default")
      (node (ref "C14") (pin "1") (pinfunction "1_1") (pintype "passive"))
      (node (ref "C16") (pin "1") (pinfunction "1_1") (pintype "passive"))
      (node (ref "C3") (pin "1") (pinfunction "1_1") (pintype "passive"))
      (node (ref "C4") (pin "2") (pinfunction "2_2") (pintype "passive"))
      (node (ref "R4") (pin "2") (pinfunction "2_2") (pintype "passive"))
      (node (ref "U2") (pin "1") (pinfunction "CLKIN_1") (pintype "passive"))
      (node (ref "U2") (pin "11") (pinfunction "FSYNC_11") (pintype "passive"))
      (node (ref "U2") (pin "18") (pinfunction "GND_18") (pintype "passive"))
      (node (ref "U2") (pin "9") (pinfunction "AD0_9") (pintype "passive"))
    )
    (net (code "56") (name "Net-(D1-K)") (class "Default")
      (node (ref "D1") (pin "2") (pinfunction "K_2") (pintype "passive"))
      (node (ref "M1") (pin "1") (pinfunction "UART_TXD_1") (pintype "passive"))
    )
    (net (code "57") (name "Net-(D2-A)") (class "Default")
      (node (ref "D2") (pin "1") (pinfunction "A_1") (pintype "passive"))
      (node (ref "M1") (pin "2") (pinfunction "UART_RXD_2") (pintype "passive"))
      (node (ref "R9") (pin "1") (pinfunction "1_1") (pintype "passive"))
    )
    (net (code "58") (name "Net-(LED1-A)") (class "Default")
      (node (ref "LED1") (pin "1") (pinfunction "A_1") (pintype "passive"))
      (node (ref "R16") (pin "1") (pinfunction "1_1") (pintype "passive"))
    )
    (net (code "59") (name "Net-(LED7-A)") (class "Default")
      (node (ref "LED7") (pin "1") (pinfunction "A_1") (pintype "passive"))
      (node (ref "R13") (pin "1") (pinfunction "1_1") (pintype "passive"))
    )
    (net (code "60") (name "Net-(U2-CPOUT)") (class "Default")
      (node (ref "C3") (pin "2") (pinfunction "2_2") (pintype "passive"))
      (node (ref "U2") (pin "20") (pinfunction "CPOUT_20") (pintype "passive"))
    )
    (net (code "61") (name "Net-(U2-REGOUT)") (class "Default")
      (node (ref "C14") (pin "2") (pinfunction "2_2") (pintype "passive"))
      (node (ref "U2") (pin "10") (pinfunction "REGOUT_10") (pintype "passive"))
    )
    (net (code "62") (name "Net-(U3-*RST)") (class "Default")
      (node (ref "R12") (pin "2") (pinfunction "2_2") (pintype "passive"))
      (node (ref "U3") (pin "9") (pinfunction "*RST_9") (pintype "passive"))
    )
    (net (code "63") (name "Net-(U3-TXD)") (class "Default")
      (node (ref "R15") (pin "2") (pinfunction "2_2") (pintype "passive"))
      (node (ref "U3") (pin "26") (pinfunction "TXD_26") (pintype "passive"))
    )
    (net (code "64") (name "Net-(U6--INA)") (class "Default")
      (node (ref "R35") (pin "1") (pinfunction "1_1") (pintype "passive"))
      (node (ref "R37") (pin "1") (pinfunction "1_1") (pintype "passive"))
      (node (ref "U6") (pin "2") (pinfunction "-INA_2") (pintype "passive"))
    )
    (net (code "65") (name "Net-(U6--INB)") (class "Default")
      (node (ref "R43") (pin "2") (pinfunction "2_2") (pintype "passive"))
      (node (ref "R46") (pin "1") (pinfunction "1_1") (pintype "passive"))
      (node (ref "U6") (pin "6") (pinfunction "-INB_6") (pintype "passive"))
    )
    (net (code "66") (name "Net-(U6--INC)") (class "Default")
      (node (ref "R44") (pin "1") (pinfunction "1_1") (pintype "passive"))
      (node (ref "R45") (pin "2") (pinfunction "2_2") (pintype "passive"))
      (node (ref "U6") (pin "9") (pinfunction "-INC_9") (pintype "passive"))
    )
    (net (code "67") (name "Net-(U6--IND)") (class "Default")
      (node (ref "R36") (pin "2") (pinfunction "2_2") (pintype "passive"))
      (node (ref "R38") (pin "2") (pinfunction "2_2") (pintype "passive"))
      (node (ref "U6") (pin "13") (pinfunction "-IND_13") (pintype "passive"))
    )
    (net (code "68") (name "Typec_5V") (class "Default")
      (node (ref "R12") (pin "1") (pinfunction "1_1") (pintype "passive"))
      (node (ref "R13") (pin "2") (pinfunction "2_2") (pintype "passive"))
      (node (ref "U3") (pin "7") (pinfunction "REGIN_7") (pintype "passive"))
      (node (ref "U3") (pin "8") (pinfunction "VBUS_8") (pintype "passive"))
      (node (ref "USB1") (pin "A4") (pinfunction "VBUS_A4") (pintype "passive"))
      (node (ref "USB1") (pin "A9") (pinfunction "VBUS_A9") (pintype "passive"))
      (node (ref "USB1") (pin "B4") (pinfunction "VBUS_B4") (pintype "passive"))
      (node (ref "USB1") (pin "B9") (pinfunction "VBUS_B9") (pintype "passive"))
    )
    (net (code "69") (name "unconnected-(IC1-Y12-Pad14)") (class "Default")
      (node (ref "IC1") (pin "14") (pinfunction "Y12_14") (pintype "output"))
    )
    (net (code "70") (name "unconnected-(IC1-Y13-Pad15)") (class "Default")
      (node (ref "IC1") (pin "15") (pinfunction "Y13_15") (pintype "output"))
    )
    (net (code "71") (name "unconnected-(IC1-Y14-Pad16)") (class "Default")
      (node (ref "IC1") (pin "16") (pinfunction "Y14_16") (pintype "output"))
    )
    (net (code "72") (name "unconnected-(IC1-Y15-Pad17)") (class "Default")
      (node (ref "IC1") (pin "17") (pinfunction "Y15_17") (pintype "output"))
    )
    (net (code "73") (name "unconnected-(IC2-VREF-Pad5)") (class "Default")
      (node (ref "IC2") (pin "5") (pinfunction "VREF_5") (pintype "passive+no_connect"))
    )
    (net (code "74") (name "unconnected-(M1-AIO0-Pad9)") (class "Default")
      (node (ref "M1") (pin "9") (pinfunction "AIO0_9") (pintype "passive+no_connect"))
    )
    (net (code "75") (name "unconnected-(M1-AIO1-Pad10)") (class "Default")
      (node (ref "M1") (pin "10") (pinfunction "AIO1_10") (pintype "passive+no_connect"))
    )
    (net (code "76") (name "unconnected-(M1-CLK-Pad19)") (class "Default")
      (node (ref "M1") (pin "19") (pinfunction "CLK_19") (pintype "passive+no_connect"))
    )
    (net (code "77") (name "unconnected-(M1-CSB-Pad16)") (class "Default")
      (node (ref "M1") (pin "16") (pinfunction "CSB_16") (pintype "passive+no_connect"))
    )
    (net (code "78") (name "unconnected-(M1-CTS-Pad3)") (class "Default")
      (node (ref "M1") (pin "3") (pinfunction "CTS_3") (pintype "passive+no_connect"))
    )
    (net (code "79") (name "unconnected-(M1-GND-Pad21)") (class "Default")
      (node (ref "M1") (pin "21") (pinfunction "GND_21") (pintype "passive+no_connect"))
    )
    (net (code "80") (name "unconnected-(M1-MISO-Pad18)") (class "Default")
      (node (ref "M1") (pin "18") (pinfunction "MISO_18") (pintype "passive+no_connect"))
    )
    (net (code "81") (name "unconnected-(M1-MOSI-Pad17)") (class "Default")
      (node (ref "M1") (pin "17") (pinfunction "MOSI_17") (pintype "passive+no_connect"))
    )
    (net (code "82") (name "unconnected-(M1-NC-Pad14)") (class "Default")
      (node (ref "M1") (pin "14") (pinfunction "NC_14") (pintype "passive+no_connect"))
    )
    (net (code "83") (name "unconnected-(M1-PCM_CLK-Pad5)") (class "Default")
      (node (ref "M1") (pin "5") (pinfunction "PCM_CLK_5") (pintype "passive+no_connect"))
    )
    (net (code "84") (name "unconnected-(M1-PCM_IN-Pad7)") (class "Default")
      (node (ref "M1") (pin "7") (pinfunction "PCM_IN_7") (pintype "passive+no_connect"))
    )
    (net (code "85") (name "unconnected-(M1-PCM_OUT-Pad6)") (class "Default")
      (node (ref "M1") (pin "6") (pinfunction "PCM_OUT_6") (pintype "passive+no_connect"))
    )
    (net (code "86") (name "unconnected-(M1-PCM_SYNC-Pad8)") (class "Default")
      (node (ref "M1") (pin "8") (pinfunction "PCM_SYNC_8") (pintype "passive+no_connect"))
    )
    (net (code "87") (name "unconnected-(M1-PIO0-Pad23)") (class "Default")
      (node (ref "M1") (pin "23") (pinfunction "PIO0_23") (pintype "passive+no_connect"))
    )
    (net (code "88") (name "unconnected-(M1-PIO1-Pad24)") (class "Default")
      (node (ref "M1") (pin "24") (pinfunction "PIO1_24") (pintype "passive+no_connect"))
    )
    (net (code "89") (name "unconnected-(M1-PIO2-Pad25)") (class "Default")
      (node (ref "M1") (pin "25") (pinfunction "PIO2_25") (pintype "passive+no_connect"))
    )
    (net (code "90") (name "unconnected-(M1-PIO3-Pad26)") (class "Default")
      (node (ref "M1") (pin "26") (pinfunction "PIO3_26") (pintype "passive+no_connect"))
    )
    (net (code "91") (name "unconnected-(M1-PIO4-Pad27)") (class "Default")
      (node (ref "M1") (pin "27") (pinfunction "PIO4_27") (pintype "passive+no_connect"))
    )
    (net (code "92") (name "unconnected-(M1-PIO5-Pad28)") (class "Default")
      (node (ref "M1") (pin "28") (pinfunction "PIO5_28") (pintype "passive+no_connect"))
    )
    (net (code "93") (name "unconnected-(M1-PIO6-Pad29)") (class "Default")
      (node (ref "M1") (pin "29") (pinfunction "PIO6_29") (pintype "passive+no_connect"))
    )
    (net (code "94") (name "unconnected-(M1-PIO7-Pad30)") (class "Default")
      (node (ref "M1") (pin "30") (pinfunction "PIO7_30") (pintype "passive+no_connect"))
    )
    (net (code "95") (name "unconnected-(M1-PIO8-Pad31)") (class "Default")
      (node (ref "M1") (pin "31") (pinfunction "PIO8_31") (pintype "passive+no_connect"))
    )
    (net (code "96") (name "unconnected-(M1-PIO9-Pad32)") (class "Default")
      (node (ref "M1") (pin "32") (pinfunction "PIO9_32") (pintype "passive+no_connect"))
    )
    (net (code "97") (name "unconnected-(M1-PIO10-Pad33)") (class "Default")
      (node (ref "M1") (pin "33") (pinfunction "PIO10_33") (pintype "passive+no_connect"))
    )
    (net (code "98") (name "unconnected-(M1-PIO11-Pad34)") (class "Default")
      (node (ref "M1") (pin "34") (pinfunction "PIO11_34") (pintype "passive+no_connect"))
    )
    (net (code "99") (name "unconnected-(M1-RESET-Pad11)") (class "Default")
      (node (ref "M1") (pin "11") (pinfunction "RESET_11") (pintype "passive+no_connect"))
    )
    (net (code "100") (name "unconnected-(M1-RT3-Pad4)") (class "Default")
      (node (ref "M1") (pin "4") (pinfunction "RT3_4") (pintype "passive+no_connect"))
    )
    (net (code "101") (name "unconnected-(M1-USB_D+-Pad20)") (class "Default")
      (node (ref "M1") (pin "20") (pinfunction "USB_D+_20") (pintype "passive+no_connect"))
    )
    (net (code "102") (name "unconnected-(M1-USB_D--Pad15)") (class "Default")
      (node (ref "M1") (pin "15") (pinfunction "USB_D-_15") (pintype "passive+no_connect"))
    )
    (net (code "103") (name "unconnected-(U1-NRST-Pad7)") (class "Default")
      (node (ref "U1") (pin "7") (pinfunction "NRST_7") (pintype "bidirectional"))
    )
    (net (code "104") (name "unconnected-(U1-PA8{slash}TIM1_CH1-Pad29)") (class "Default")
      (node (ref "U1") (pin "29") (pinfunction "PA8/TIM1_CH1_29") (pintype "bidirectional"))
    )
    (net (code "105") (name "unconnected-(U1-PA15{slash}JTDI-Pad38)") (class "Default")
      (node (ref "U1") (pin "38") (pinfunction "PA15/JTDI_38") (pintype "bidirectional"))
    )
    (net (code "106") (name "unconnected-(U1-PB2{slash}BOOT1-Pad20)") (class "Default")
      (node (ref "U1") (pin "20") (pinfunction "PB2/BOOT1_20") (pintype "bidirectional"))
    )
    (net (code "107") (name "unconnected-(U1-PB3{slash}JTDO-Pad39)") (class "Default")
      (node (ref "U1") (pin "39") (pinfunction "PB3/JTDO_39") (pintype "bidirectional"))
    )
    (net (code "108") (name "unconnected-(U1-PB4{slash}JNTRST-Pad40)") (class "Default")
      (node (ref "U1") (pin "40") (pinfunction "PB4/JNTRST_40") (pintype "bidirectional"))
    )
    (net (code "109") (name "unconnected-(U1-PB5-Pad41)") (class "Default")
      (node (ref "U1") (pin "41") (pinfunction "PB5_41") (pintype "bidirectional"))
    )
    (net (code "110") (name "unconnected-(U1-PC13-TAMPER-RTC-Pad2)") (class "Default")
      (node (ref "U1") (pin "2") (pinfunction "PC13-TAMPER-RTC_2") (pintype "bidirectional"))
    )
    (net (code "111") (name "unconnected-(U1-PC14-OSC32_IN-Pad3)") (class "Default")
      (node (ref "U1") (pin "3") (pinfunction "PC14-OSC32_IN_3") (pintype "bidirectional"))
    )
    (net (code "112") (name "unconnected-(U1-PC15-OSC32_OUT-Pad4)") (class "Default")
      (node (ref "U1") (pin "4") (pinfunction "PC15-OSC32_OUT_4") (pintype "bidirectional"))
    )
    (net (code "113") (name "unconnected-(U1-SPI2_MISO{slash}PB14-Pad27)") (class "Default")
      (node (ref "U1") (pin "27") (pinfunction "SPI2_MISO/PB14_27") (pintype "bidirectional"))
    )
    (net (code "114") (name "unconnected-(U1-SPI2_MOSI{slash}PB15-Pad28)") (class "Default")
      (node (ref "U1") (pin "28") (pinfunction "SPI2_MOSI/PB15_28") (pintype "bidirectional"))
    )
    (net (code "115") (name "unconnected-(U1-SPI2_NSS{slash}PB12-Pad25)") (class "Default")
      (node (ref "U1") (pin "25") (pinfunction "SPI2_NSS/PB12_25") (pintype "bidirectional"))
    )
    (net (code "116") (name "unconnected-(U1-SPI2_SCK{slash}PB13-Pad26)") (class "Default")
      (node (ref "U1") (pin "26") (pinfunction "SPI2_SCK/PB13_26") (pintype "bidirectional"))
    )
    (net (code "117") (name "unconnected-(U1-TIM3_CH4{slash}PB1-Pad19)") (class "Default")
      (node (ref "U1") (pin "19") (pinfunction "TIM3_CH4/PB1_19") (pintype "bidirectional"))
    )
    (net (code "118") (name "unconnected-(U1-TIM4_CH1{slash}PB6-Pad42)") (class "Default")
      (node (ref "U1") (pin "42") (pinfunction "TIM4_CH1/PB6_42") (pintype "bidirectional"))
    )
    (net (code "119") (name "unconnected-(U1-TIM4_CH2{slash}PB7-Pad43)") (class "Default")
      (node (ref "U1") (pin "43") (pinfunction "TIM4_CH2/PB7_43") (pintype "bidirectional"))
    )
    (net (code "120") (name "unconnected-(U1-TIM4_CH3{slash}PB8-Pad45)") (class "Default")
      (node (ref "U1") (pin "45") (pinfunction "TIM4_CH3/PB8_45") (pintype "bidirectional"))
    )
    (net (code "121") (name "unconnected-(U1-TIM4_CH4{slash}PB9-Pad46)") (class "Default")
      (node (ref "U1") (pin "46") (pinfunction "TIM4_CH4/PB9_46") (pintype "bidirectional"))
    )
    (net (code "122") (name "unconnected-(U2-AX_CL-Pad7)") (class "Default")
      (node (ref "U2") (pin "7") (pinfunction "AX_CL_7") (pintype "passive+no_connect"))
    )
    (net (code "123") (name "unconnected-(U2-AX_DA-Pad6)") (class "Default")
      (node (ref "U2") (pin "6") (pinfunction "AX_DA_6") (pintype "passive+no_connect"))
    )
    (net (code "124") (name "unconnected-(U2-CLKOUT-Pad22)") (class "Default")
      (node (ref "U2") (pin "22") (pinfunction "CLKOUT_22") (pintype "passive+no_connect"))
    )
    (net (code "125") (name "unconnected-(U2-INT-Pad12)") (class "Default")
      (node (ref "U2") (pin "12") (pinfunction "INT_12") (pintype "passive+no_connect"))
    )
    (net (code "126") (name "unconnected-(U2-NC-Pad2)") (class "Default")
      (node (ref "U2") (pin "2") (pinfunction "NC_2") (pintype "passive+no_connect"))
    )
    (net (code "127") (name "unconnected-(U2-NC-Pad3)") (class "Default")
      (node (ref "U2") (pin "3") (pinfunction "NC_3") (pintype "passive+no_connect"))
    )
    (net (code "128") (name "unconnected-(U2-NC-Pad4)") (class "Default")
      (node (ref "U2") (pin "4") (pinfunction "NC_4") (pintype "passive+no_connect"))
    )
    (net (code "129") (name "unconnected-(U2-NC-Pad5)") (class "Default")
      (node (ref "U2") (pin "5") (pinfunction "NC_5") (pintype "passive+no_connect"))
    )
    (net (code "130") (name "unconnected-(U2-NC-Pad14)") (class "Default")
      (node (ref "U2") (pin "14") (pinfunction "NC_14") (pintype "passive+no_connect"))
    )
    (net (code "131") (name "unconnected-(U2-NC-Pad15)") (class "Default")
      (node (ref "U2") (pin "15") (pinfunction "NC_15") (pintype "passive+no_connect"))
    )
    (net (code "132") (name "unconnected-(U2-NC-Pad16)") (class "Default")
      (node (ref "U2") (pin "16") (pinfunction "NC_16") (pintype "passive+no_connect"))
    )
    (net (code "133") (name "unconnected-(U2-NC-Pad17)") (class "Default")
      (node (ref "U2") (pin "17") (pinfunction "NC_17") (pintype "passive+no_connect"))
    )
    (net (code "134") (name "unconnected-(U2-RESV-Pad19)") (class "Default")
      (node (ref "U2") (pin "19") (pinfunction "RESV_19") (pintype "passive+no_connect"))
    )
    (net (code "135") (name "unconnected-(U2-RESV-Pad21)") (class "Default")
      (node (ref "U2") (pin "21") (pinfunction "RESV_21") (pintype "passive+no_connect"))
    )
    (net (code "136") (name "unconnected-(U3-*SUSPEND-Pad11)") (class "Default")
      (node (ref "U3") (pin "11") (pinfunction "*SUSPEND_11") (pintype "passive"))
    )
    (net (code "137") (name "unconnected-(U3-CTS-Pad23)") (class "Default")
      (node (ref "U3") (pin "23") (pinfunction "CTS_23") (pintype "passive"))
    )
    (net (code "138") (name "unconnected-(U3-DCD-Pad1)") (class "Default")
      (node (ref "U3") (pin "1") (pinfunction "DCD_1") (pintype "passive"))
    )
    (net (code "139") (name "unconnected-(U3-DSR-Pad27)") (class "Default")
      (node (ref "U3") (pin "27") (pinfunction "DSR_27") (pintype "passive"))
    )
    (net (code "140") (name "unconnected-(U3-DTR-Pad28)") (class "Default")
      (node (ref "U3") (pin "28") (pinfunction "DTR_28") (pintype "passive"))
    )
    (net (code "141") (name "unconnected-(U3-NC-Pad10)") (class "Default")
      (node (ref "U3") (pin "10") (pinfunction "NC_10") (pintype "passive"))
    )
    (net (code "142") (name "unconnected-(U3-NC-Pad13)") (class "Default")
      (node (ref "U3") (pin "13") (pinfunction "NC_13") (pintype "passive"))
    )
    (net (code "143") (name "unconnected-(U3-NC-Pad14)") (class "Default")
      (node (ref "U3") (pin "14") (pinfunction "NC_14") (pintype "passive"))
    )
    (net (code "144") (name "unconnected-(U3-NC-Pad15)") (class "Default")
      (node (ref "U3") (pin "15") (pinfunction "NC_15") (pintype "passive"))
    )
    (net (code "145") (name "unconnected-(U3-NC-Pad16)") (class "Default")
      (node (ref "U3") (pin "16") (pinfunction "NC_16") (pintype "passive"))
    )
    (net (code "146") (name "unconnected-(U3-NC-Pad17)") (class "Default")
      (node (ref "U3") (pin "17") (pinfunction "NC_17") (pintype "passive"))
    )
    (net (code "147") (name "unconnected-(U3-NC-Pad18)") (class "Default")
      (node (ref "U3") (pin "18") (pinfunction "NC_18") (pintype "passive"))
    )
    (net (code "148") (name "unconnected-(U3-NC-Pad19)") (class "Default")
      (node (ref "U3") (pin "19") (pinfunction "NC_19") (pintype "passive"))
    )
    (net (code "149") (name "unconnected-(U3-NC-Pad20)") (class "Default")
      (node (ref "U3") (pin "20") (pinfunction "NC_20") (pintype "passive"))
    )
    (net (code "150") (name "unconnected-(U3-NC-Pad21)") (class "Default")
      (node (ref "U3") (pin "21") (pinfunction "NC_21") (pintype "passive"))
    )
    (net (code "151") (name "unconnected-(U3-NC-Pad22)") (class "Default")
      (node (ref "U3") (pin "22") (pinfunction "NC_22") (pintype "passive"))
    )
    (net (code "152") (name "unconnected-(U3-RI-Pad2)") (class "Default")
      (node (ref "U3") (pin "2") (pinfunction "RI_2") (pintype "passive"))
    )
    (net (code "153") (name "unconnected-(U3-RTS-Pad24)") (class "Default")
      (node (ref "U3") (pin "24") (pinfunction "RTS_24") (pintype "passive"))
    )
    (net (code "154") (name "unconnected-(U3-SUSPEND-Pad12)") (class "Default")
      (node (ref "U3") (pin "12") (pinfunction "SUSPEND_12") (pintype "passive"))
    )
    (net (code "155") (name "unconnected-(U3-VDD-Pad6)") (class "Default")
      (node (ref "U3") (pin "6") (pinfunction "VDD_6") (pintype "passive"))
    )
    (net (code "156") (name "unconnected-(USB1-CC1-PadA5)") (class "Default")
      (node (ref "USB1") (pin "A5") (pinfunction "CC1_A5") (pintype "passive"))
    )
    (net (code "157") (name "unconnected-(USB1-CC2-PadB5)") (class "Default")
      (node (ref "USB1") (pin "B5") (pinfunction "CC2_B5") (pintype "passive"))
    )
    (net (code "158") (name "unconnected-(USB1-RX1+-PadB11)") (class "Default")
      (node (ref "USB1") (pin "B11") (pinfunction "RX1+_B11") (pintype "passive"))
    )
    (net (code "159") (name "unconnected-(USB1-RX1--PadB10)") (class "Default")
      (node (ref "USB1") (pin "B10") (pinfunction "RX1-_B10") (pintype "passive"))
    )
    (net (code "160") (name "unconnected-(USB1-RX2+-PadA11)") (class "Default")
      (node (ref "USB1") (pin "A11") (pinfunction "RX2+_A11") (pintype "passive"))
    )
    (net (code "161") (name "unconnected-(USB1-RX2--PadA10)") (class "Default")
      (node (ref "USB1") (pin "A10") (pinfunction "RX2-_A10") (pintype "passive"))
    )
    (net (code "162") (name "unconnected-(USB1-SBU1-PadA8)") (class "Default")
      (node (ref "USB1") (pin "A8") (pinfunction "SBU1_A8") (pintype "passive"))
    )
    (net (code "163") (name "unconnected-(USB1-SBU2-PadB8)") (class "Default")
      (node (ref "USB1") (pin "B8") (pinfunction "SBU2_B8") (pintype "passive"))
    )
    (net (code "164") (name "unconnected-(USB1-TX1+-PadA2)") (class "Default")
      (node (ref "USB1") (pin "A2") (pinfunction "TX1+_A2") (pintype "passive"))
    )
    (net (code "165") (name "unconnected-(USB1-TX1--PadA3)") (class "Default")
      (node (ref "USB1") (pin "A3") (pinfunction "TX1-_A3") (pintype "passive"))
    )
    (net (code "166") (name "unconnected-(USB1-TX2+-PadB2)") (class "Default")
      (node (ref "USB1") (pin "B2") (pinfunction "TX2+_B2") (pintype "passive"))
    )
    (net (code "167") (name "unconnected-(USB1-TX2--PadB3)") (class "Default")
      (node (ref "USB1") (pin "B3") (pinfunction "TX2-_B3") (pintype "passive"))
    )
  )
)
